# Lipo_Module.net
KiCad netlist of a schematic drawn in EAGLE
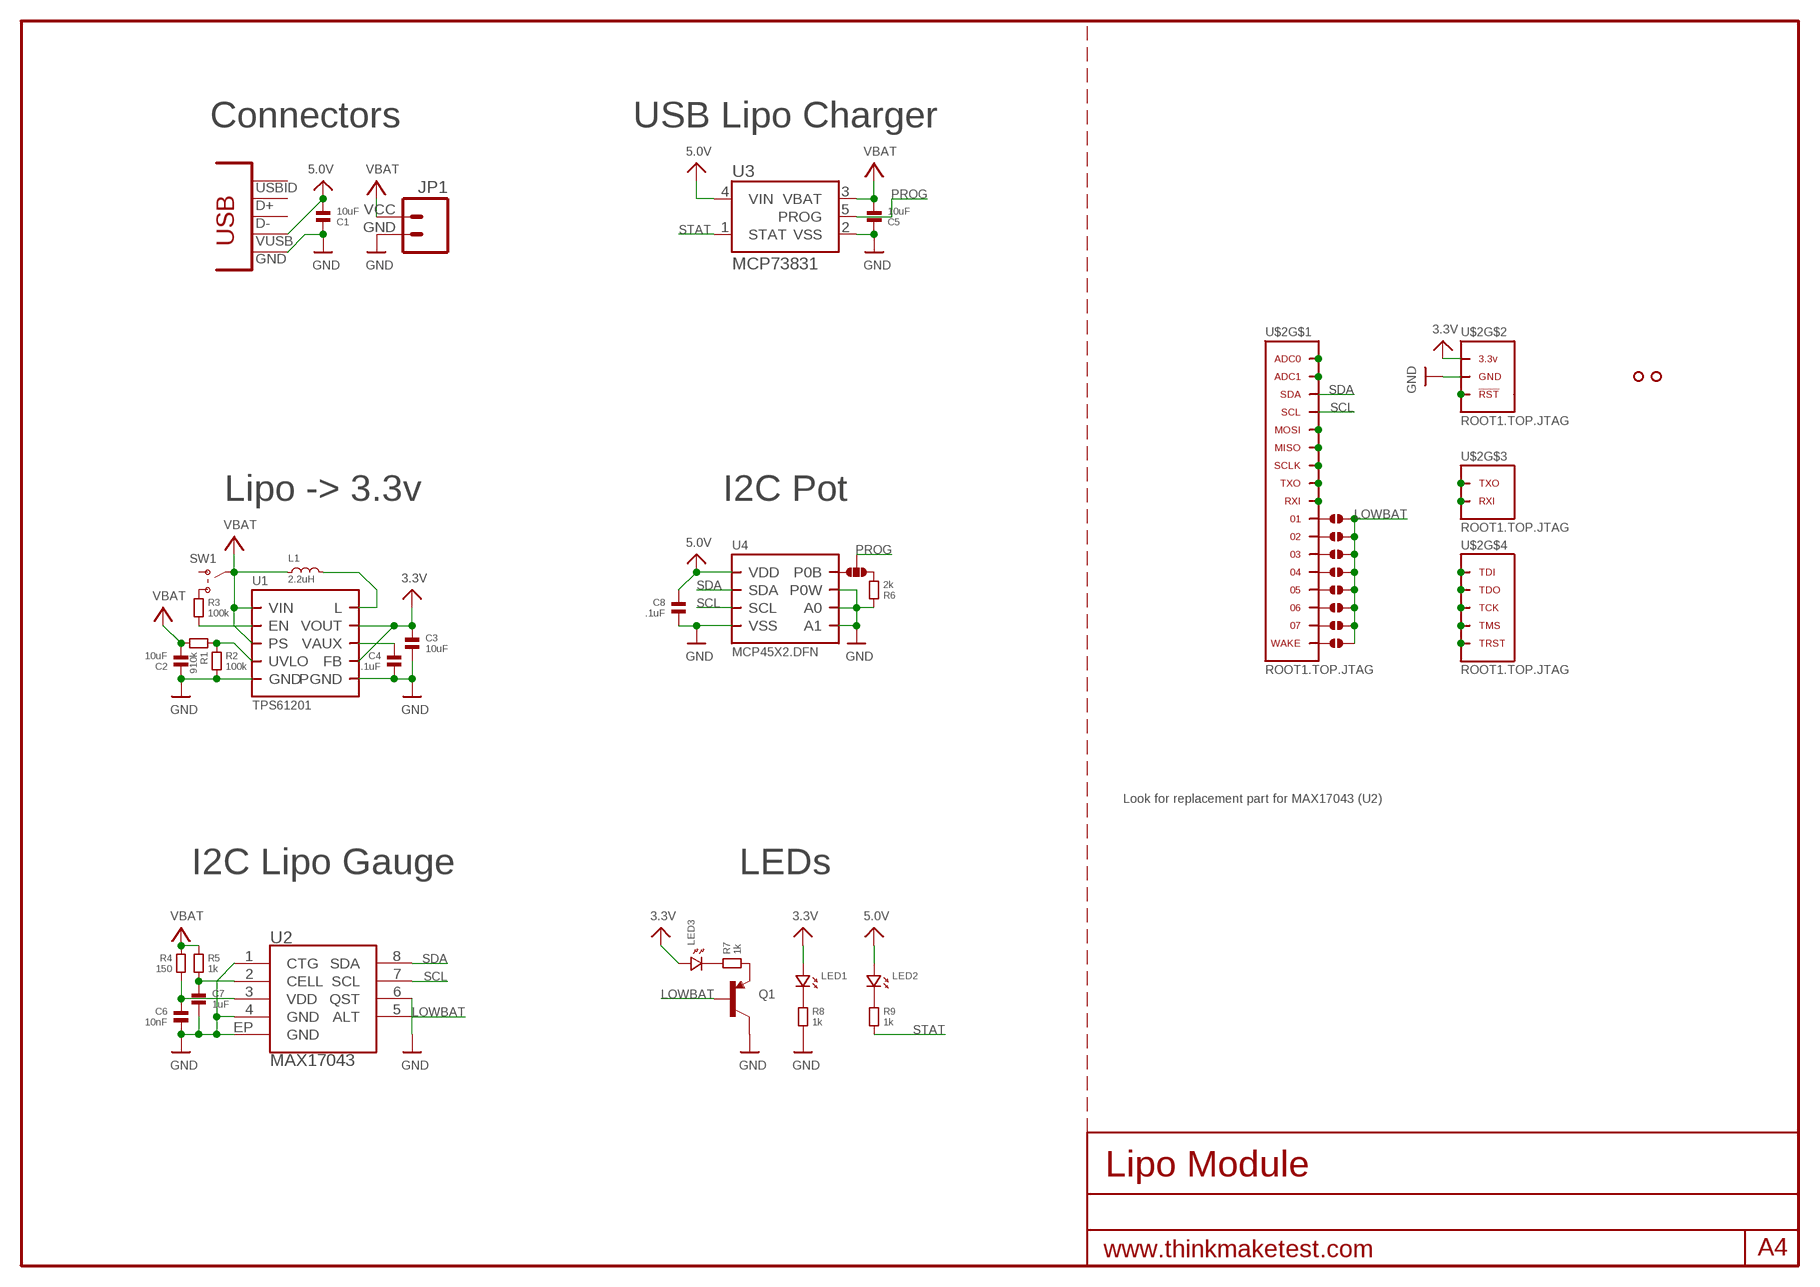
[diagram p0: schematic, sheet 1]

(export (version "E")
  (design (tool "Eeschema 10.0.6"))
  (components
    (comp (ref "C1")
      (value "10uF")
      (footprint "eagle-import:0805")
      (libsource (lib "eagle-import") (part "CAPACITOR.0805"))
    )
    (comp (ref "C2")
      (value "10uF")
      (footprint "eagle-import:0805")
      (libsource (lib "eagle-import") (part "CAPACITOR.0805"))
    )
    (comp (ref "C3")
      (value "10uF")
      (footprint "eagle-import:0805")
      (libsource (lib "eagle-import") (part "CAPACITOR.0805"))
    )
    (comp (ref "C4")
      (value ".1uF")
      (footprint "eagle-import:0603")
      (libsource (lib "eagle-import") (part "CAPACITOR.0603"))
    )
    (comp (ref "C5")
      (value "10uF")
      (footprint "eagle-import:0805")
      (libsource (lib "eagle-import") (part "CAPACITOR.0805"))
    )
    (comp (ref "C6")
      (value "10nF")
      (footprint "eagle-import:0603")
      (libsource (lib "eagle-import") (part "CAPACITOR.0603"))
    )
    (comp (ref "C7")
      (value "1uF")
      (footprint "eagle-import:0603")
      (libsource (lib "eagle-import") (part "CAPACITOR.0603"))
    )
    (comp (ref "C8")
      (value ".1uF")
      (footprint "eagle-import:0603")
      (libsource (lib "eagle-import") (part "CAPACITOR.0603"))
    )
    (comp (ref "J1")
      (value "SOLDERJUMPER.3.LRG.23")
      (footprint "eagle-import:3.LRG.23")
      (libsource (lib "eagle-import") (part "SOLDERJUMPER.3.LRG.23"))
    )
    (comp (ref "J2")
      (value "SOLDERJUMPER.2.SML")
      (footprint "eagle-import:2.SML")
      (libsource (lib "eagle-import") (part "SOLDERJUMPER.2.SML"))
    )
    (comp (ref "J3")
      (value "SOLDERJUMPER.2.SML")
      (footprint "eagle-import:2.SML")
      (libsource (lib "eagle-import") (part "SOLDERJUMPER.2.SML"))
    )
    (comp (ref "J4")
      (value "SOLDERJUMPER.2.SML")
      (footprint "eagle-import:2.SML")
      (libsource (lib "eagle-import") (part "SOLDERJUMPER.2.SML"))
    )
    (comp (ref "J5")
      (value "SOLDERJUMPER.2.SML")
      (footprint "eagle-import:2.SML")
      (libsource (lib "eagle-import") (part "SOLDERJUMPER.2.SML"))
    )
    (comp (ref "J6")
      (value "SOLDERJUMPER.2.SML")
      (footprint "eagle-import:2.SML")
      (libsource (lib "eagle-import") (part "SOLDERJUMPER.2.SML"))
    )
    (comp (ref "J7")
      (value "SOLDERJUMPER.2.SML")
      (footprint "eagle-import:2.SML")
      (libsource (lib "eagle-import") (part "SOLDERJUMPER.2.SML"))
    )
    (comp (ref "J8")
      (value "SOLDERJUMPER.2.SML")
      (footprint "eagle-import:2.SML")
      (libsource (lib "eagle-import") (part "SOLDERJUMPER.2.SML"))
    )
    (comp (ref "J9")
      (value "SOLDERJUMPER.2.SML")
      (footprint "eagle-import:2.SML")
      (libsource (lib "eagle-import") (part "SOLDERJUMPER.2.SML"))
    )
    (comp (ref "JP1")
      (value "M024UCON-15767")
      (footprint "eagle-import:JST-2-SMD-VERT")
      (libsource (lib "eagle-import") (part "M024UCON-15767"))
    )
    (comp (ref "L1")
      (value "2.2uH")
      (footprint "eagle-import:SRN3015")
      (libsource (lib "eagle-import") (part "INDUCTOR-SRN3015"))
    )
    (comp (ref "LED1")
      (value "LED.0603")
      (footprint "eagle-import:0603.LED")
      (libsource (lib "eagle-import") (part "LED.0603"))
    )
    (comp (ref "LED2")
      (value "LED.0603")
      (footprint "eagle-import:0603.LED")
      (libsource (lib "eagle-import") (part "LED.0603"))
    )
    (comp (ref "LED3")
      (value "LED.0603")
      (footprint "eagle-import:0603.LED")
      (libsource (lib "eagle-import") (part "LED.0603"))
    )
    (comp (ref "Q1")
      (value "TRANSISTOR_PNPSOT23-REFLOW")
      (footprint "eagle-import:SOT23-R")
      (libsource (lib "eagle-import") (part "TRANSISTOR_PNPSOT23-REFLOW"))
    )
    (comp (ref "R1")
      (value "910k")
      (footprint "eagle-import:0603")
      (libsource (lib "eagle-import") (part "RESISTOR.0603"))
    )
    (comp (ref "R2")
      (value "100k")
      (footprint "eagle-import:0603")
      (libsource (lib "eagle-import") (part "RESISTOR.0603"))
    )
    (comp (ref "R3")
      (value "100k")
      (footprint "eagle-import:0603")
      (libsource (lib "eagle-import") (part "RESISTOR.0603"))
    )
    (comp (ref "R4")
      (value "150")
      (footprint "eagle-import:0603")
      (libsource (lib "eagle-import") (part "RESISTOR.0603"))
    )
    (comp (ref "R5")
      (value "1k")
      (footprint "eagle-import:0603")
      (libsource (lib "eagle-import") (part "RESISTOR.0603"))
    )
    (comp (ref "R6")
      (value "2k")
      (footprint "eagle-import:0603")
      (libsource (lib "eagle-import") (part "RESISTOR.0603"))
    )
    (comp (ref "R7")
      (value "1k")
      (footprint "eagle-import:0603")
      (libsource (lib "eagle-import") (part "RESISTOR.0603"))
    )
    (comp (ref "R8")
      (value "1k")
      (footprint "eagle-import:0603")
      (libsource (lib "eagle-import") (part "RESISTOR.0603"))
    )
    (comp (ref "R9")
      (value "1k")
      (footprint "eagle-import:0603")
      (libsource (lib "eagle-import") (part "RESISTOR.0603"))
    )
    (comp (ref "SW1")
      (value "SSSS810701")
      (footprint "eagle-import:SSSS810701")
      (libsource (lib "eagle-import") (part "SSSS810701"))
    )
    (comp (ref "U$2")
      (value "ROOT1.TOP.JTAG")
      (footprint "eagle-import:ROOT1.TOP")
      (libsource (lib "eagle-import") (part "ROOT1.TOP.JTAG"))
    )
    (comp (ref "U$3")
      (value "HOLE.2MM")
      (footprint "eagle-import:2MM")
      (libsource (lib "eagle-import") (part "HOLE.2MM"))
    )
    (comp (ref "U$4")
      (value "HOLE.2MM")
      (footprint "eagle-import:2MM")
      (libsource (lib "eagle-import") (part "HOLE.2MM"))
    )
    (comp (ref "U1")
      (value "TPS61201")
      (footprint "eagle-import:DRC")
      (libsource (lib "eagle-import") (part "TPS6120X"))
    )
    (comp (ref "U2")
      (value "MAX17043")
      (footprint "eagle-import:TDFN-8")
      (libsource (lib "eagle-import") (part "MAX1704X"))
    )
    (comp (ref "U3")
      (value "MCP73831")
      (footprint "eagle-import:SOT23-5")
      (libsource (lib "eagle-import") (part "MCP73831"))
    )
    (comp (ref "U4")
      (value "MCP45X2.DFN")
      (footprint "eagle-import:DFN-8.3X3.PAD")
      (libsource (lib "eagle-import") (part "MCP45X2.DFN"))
    )
    (comp (ref "USB1")
      (value "CON-USB-F-MICRO-B")
      (footprint "eagle-import:CONN_USB_MICRO-B")
      (libsource (lib "eagle-import") (part "CON-USB-F-MICRO-B"))
    )
  )
  (nets
    (net (code "1") (name "/LOWBAT") (class "Default")
      (node (ref "J2") (pin "2") (pinfunction "2_2") (pintype "bidirectional"))
      (node (ref "J3") (pin "2") (pinfunction "2_2") (pintype "bidirectional"))
      (node (ref "J4") (pin "2") (pinfunction "2_2") (pintype "bidirectional"))
      (node (ref "J5") (pin "2") (pinfunction "2_2") (pintype "bidirectional"))
      (node (ref "J6") (pin "2") (pinfunction "2_2") (pintype "bidirectional"))
      (node (ref "J7") (pin "2") (pinfunction "2_2") (pintype "bidirectional"))
      (node (ref "J8") (pin "2") (pinfunction "2_2") (pintype "bidirectional"))
      (node (ref "J9") (pin "2") (pinfunction "2_2") (pintype "bidirectional"))
      (node (ref "Q1") (pin "1") (pinfunction "B_1") (pintype "passive"))
      (node (ref "U2") (pin "5") (pinfunction "ALT_5") (pintype "bidirectional"))
    )
    (net (code "2") (name "/PROG") (class "Default")
      (node (ref "J1") (pin "2") (pinfunction "2_2") (pintype "bidirectional"))
      (node (ref "U3") (pin "5") (pinfunction "PROG_5") (pintype "input"))
    )
    (net (code "3") (name "/SCL") (class "Default")
      (node (ref "U$2") (pin "SCL") (pinfunction "SCL_SCL") (pintype "bidirectional"))
      (node (ref "U2") (pin "7") (pinfunction "SCL_7") (pintype "bidirectional"))
      (node (ref "U4") (pin "2") (pinfunction "SCL_2") (pintype "bidirectional"))
    )
    (net (code "4") (name "/SDA") (class "Default")
      (node (ref "U$2") (pin "SDA") (pinfunction "SDA_SDA") (pintype "bidirectional"))
      (node (ref "U2") (pin "8") (pinfunction "SDA_8") (pintype "bidirectional"))
      (node (ref "U4") (pin "3") (pinfunction "SDA_3") (pintype "bidirectional"))
    )
    (net (code "5") (name "/STAT") (class "Default")
      (node (ref "R9") (pin "2") (pinfunction "2_2") (pintype "bidirectional"))
      (node (ref "U3") (pin "1") (pinfunction "STAT_1") (pintype "output"))
    )
    (net (code "6") (name "3.3V") (class "Default")
      (node (ref "C3") (pin "1") (pinfunction "1_1") (pintype "bidirectional"))
      (node (ref "LED1") (pin "P$1") (pinfunction "1_P$1") (pintype "bidirectional"))
      (node (ref "LED3") (pin "P$1") (pinfunction "1_P$1") (pintype "bidirectional"))
      (node (ref "U$2") (pin "3.3V@1") (pinfunction "3.3V_3.3V@1") (pintype "bidirectional"))
      (node (ref "U$2") (pin "3.3V@10") (pinfunction "3.3V_3.3V@10") (pintype "bidirectional"))
      (node (ref "U$2") (pin "3.3V@11") (pinfunction "3.3V_3.3V@11") (pintype "bidirectional"))
      (node (ref "U$2") (pin "3.3V@12") (pinfunction "3.3V_3.3V@12") (pintype "bidirectional"))
      (node (ref "U$2") (pin "3.3V@2") (pinfunction "3.3V_3.3V@2") (pintype "bidirectional"))
      (node (ref "U$2") (pin "3.3V@3") (pinfunction "3.3V_3.3V@3") (pintype "bidirectional"))
      (node (ref "U$2") (pin "3.3V@4") (pinfunction "3.3V_3.3V@4") (pintype "bidirectional"))
      (node (ref "U$2") (pin "3.3V@5") (pinfunction "3.3V_3.3V@5") (pintype "bidirectional"))
      (node (ref "U$2") (pin "3.3V@6") (pinfunction "3.3V_3.3V@6") (pintype "bidirectional"))
      (node (ref "U$2") (pin "3.3V@7") (pinfunction "3.3V_3.3V@7") (pintype "bidirectional"))
      (node (ref "U$2") (pin "3.3V@8") (pinfunction "3.3V_3.3V@8") (pintype "bidirectional"))
      (node (ref "U$2") (pin "3.3V@9") (pinfunction "3.3V_3.3V@9") (pintype "bidirectional"))
      (node (ref "U1") (pin "10") (pinfunction "FB_10") (pintype "bidirectional"))
      (node (ref "U1") (pin "2") (pinfunction "VOUT_2") (pintype "bidirectional"))
    )
    (net (code "7") (name "5.0V") (class "Default")
      (node (ref "C1") (pin "2") (pinfunction "2_2") (pintype "bidirectional"))
      (node (ref "C8") (pin "1") (pinfunction "1_1") (pintype "bidirectional"))
      (node (ref "LED2") (pin "P$1") (pinfunction "1_P$1") (pintype "bidirectional"))
      (node (ref "U3") (pin "4") (pinfunction "VIN_4") (pintype "power_in"))
      (node (ref "U4") (pin "8") (pinfunction "VDD_8") (pintype "bidirectional"))
      (node (ref "USB1") (pin "P1") (pinfunction "VUSB_P1") (pintype "bidirectional"))
    )
    (net (code "8") (name "GND") (class "Default")
      (node (ref "C1") (pin "1") (pinfunction "1_1") (pintype "bidirectional"))
      (node (ref "C2") (pin "1") (pinfunction "1_1") (pintype "bidirectional"))
      (node (ref "C3") (pin "2") (pinfunction "2_2") (pintype "bidirectional"))
      (node (ref "C4") (pin "2") (pinfunction "2_2") (pintype "bidirectional"))
      (node (ref "C5") (pin "1") (pinfunction "1_1") (pintype "bidirectional"))
      (node (ref "C6") (pin "2") (pinfunction "2_2") (pintype "bidirectional"))
      (node (ref "C7") (pin "2") (pinfunction "2_2") (pintype "bidirectional"))
      (node (ref "C8") (pin "2") (pinfunction "2_2") (pintype "bidirectional"))
      (node (ref "JP1") (pin "GND") (pinfunction "1_GND") (pintype "passive"))
      (node (ref "Q1") (pin "3") (pinfunction "C_3") (pintype "passive"))
      (node (ref "R2") (pin "2") (pinfunction "2_2") (pintype "bidirectional"))
      (node (ref "R6") (pin "1") (pinfunction "1_1") (pintype "bidirectional"))
      (node (ref "R8") (pin "2") (pinfunction "2_2") (pintype "bidirectional"))
      (node (ref "U$2") (pin "GND@1") (pinfunction "GND_GND@1") (pintype "bidirectional"))
      (node (ref "U$2") (pin "GND@10") (pinfunction "GND_GND@10") (pintype "bidirectional"))
      (node (ref "U$2") (pin "GND@11") (pinfunction "GND_GND@11") (pintype "bidirectional"))
      (node (ref "U$2") (pin "GND@12") (pinfunction "GND_GND@12") (pintype "bidirectional"))
      (node (ref "U$2") (pin "GND@13") (pinfunction "GND_GND@13") (pintype "bidirectional"))
      (node (ref "U$2") (pin "GND@2") (pinfunction "GND_GND@2") (pintype "bidirectional"))
      (node (ref "U$2") (pin "GND@3") (pinfunction "GND_GND@3") (pintype "bidirectional"))
      (node (ref "U$2") (pin "GND@4") (pinfunction "GND_GND@4") (pintype "bidirectional"))
      (node (ref "U$2") (pin "GND@5") (pinfunction "GND_GND@5") (pintype "bidirectional"))
      (node (ref "U$2") (pin "GND@6") (pinfunction "GND_GND@6") (pintype "bidirectional"))
      (node (ref "U$2") (pin "GND@7") (pinfunction "GND_GND@7") (pintype "bidirectional"))
      (node (ref "U$2") (pin "GND@8") (pinfunction "GND_GND@8") (pintype "bidirectional"))
      (node (ref "U$2") (pin "GND@9") (pinfunction "GND_GND@9") (pintype "bidirectional"))
      (node (ref "U1") (pin "4") (pinfunction "PGND_4") (pintype "bidirectional"))
      (node (ref "U1") (pin "9") (pinfunction "GND_9") (pintype "bidirectional"))
      (node (ref "U1") (pin "PAD") (pinfunction "PGND_PAD") (pintype "bidirectional"))
      (node (ref "U2") (pin "1") (pinfunction "CTG_1") (pintype "bidirectional"))
      (node (ref "U2") (pin "4") (pinfunction "GND_4") (pintype "bidirectional"))
      (node (ref "U2") (pin "6") (pinfunction "QST_6") (pintype "bidirectional"))
      (node (ref "U2") (pin "EP") (pinfunction "GND_EP") (pintype "bidirectional"))
      (node (ref "U3") (pin "2") (pinfunction "VSS_2") (pintype "power_in"))
      (node (ref "U4") (pin "1") (pinfunction "A0_1") (pintype "bidirectional"))
      (node (ref "U4") (pin "4") (pinfunction "VSS_4") (pintype "bidirectional"))
      (node (ref "U4") (pin "5") (pinfunction "P0W_5") (pintype "bidirectional"))
      (node (ref "U4") (pin "7") (pinfunction "A1_7") (pintype "bidirectional"))
      (node (ref "U4") (pin "PAD") (pinfunction "VSS_PAD") (pintype "bidirectional"))
      (node (ref "USB1") (pin "P5") (pinfunction "GND_P5") (pintype "bidirectional"))
    )
    (net (code "9") (name "Net-(J1-Pad3)") (class "Default")
      (node (ref "J1") (pin "3") (pinfunction "3_3") (pintype "bidirectional"))
      (node (ref "R6") (pin "2") (pinfunction "2_2") (pintype "bidirectional"))
    )
    (net (code "10") (name "Net-(J2-Pad1)") (class "Default")
      (node (ref "J2") (pin "1") (pinfunction "1_1") (pintype "bidirectional"))
      (node (ref "U$2") (pin "01") (pinfunction "01_01") (pintype "bidirectional"))
    )
    (net (code "11") (name "Net-(J3-Pad1)") (class "Default")
      (node (ref "J3") (pin "1") (pinfunction "1_1") (pintype "bidirectional"))
      (node (ref "U$2") (pin "02") (pinfunction "02_02") (pintype "bidirectional"))
    )
    (net (code "12") (name "Net-(J4-Pad1)") (class "Default")
      (node (ref "J4") (pin "1") (pinfunction "1_1") (pintype "bidirectional"))
      (node (ref "U$2") (pin "03") (pinfunction "03_03") (pintype "bidirectional"))
    )
    (net (code "13") (name "Net-(J5-Pad1)") (class "Default")
      (node (ref "J5") (pin "1") (pinfunction "1_1") (pintype "bidirectional"))
      (node (ref "U$2") (pin "04") (pinfunction "04_04") (pintype "bidirectional"))
    )
    (net (code "14") (name "Net-(J6-Pad1)") (class "Default")
      (node (ref "J6") (pin "1") (pinfunction "1_1") (pintype "bidirectional"))
      (node (ref "U$2") (pin "05") (pinfunction "05_05") (pintype "bidirectional"))
    )
    (net (code "15") (name "Net-(J7-Pad1)") (class "Default")
      (node (ref "J7") (pin "1") (pinfunction "1_1") (pintype "bidirectional"))
      (node (ref "U$2") (pin "06") (pinfunction "06_06") (pintype "bidirectional"))
    )
    (net (code "16") (name "Net-(J8-Pad1)") (class "Default")
      (node (ref "J8") (pin "1") (pinfunction "1_1") (pintype "bidirectional"))
      (node (ref "U$2") (pin "07") (pinfunction "07_07") (pintype "bidirectional"))
    )
    (net (code "17") (name "Net-(J9-Pad1)") (class "Default")
      (node (ref "J9") (pin "1") (pinfunction "1_1") (pintype "bidirectional"))
      (node (ref "U$2") (pin "WAKE") (pinfunction "WAKE_WAKE") (pintype "bidirectional"))
    )
    (net (code "18") (name "Net-(LED1-2)") (class "Default")
      (node (ref "LED1") (pin "P$2") (pinfunction "2_P$2") (pintype "bidirectional"))
      (node (ref "R8") (pin "1") (pinfunction "1_1") (pintype "bidirectional"))
    )
    (net (code "19") (name "Net-(LED2-2)") (class "Default")
      (node (ref "LED2") (pin "P$2") (pinfunction "2_P$2") (pintype "bidirectional"))
      (node (ref "R9") (pin "1") (pinfunction "1_1") (pintype "bidirectional"))
    )
    (net (code "20") (name "Net-(LED3-2)") (class "Default")
      (node (ref "LED3") (pin "P$2") (pinfunction "2_P$2") (pintype "bidirectional"))
      (node (ref "R7") (pin "1") (pinfunction "1_1") (pintype "bidirectional"))
    )
    (net (code "21") (name "Net-(Q1-E)") (class "Default")
      (node (ref "Q1") (pin "2") (pinfunction "E_2") (pintype "passive"))
      (node (ref "R7") (pin "2") (pinfunction "2_2") (pintype "bidirectional"))
    )
    (net (code "22") (name "Net-(SW1-B)") (class "Default")
      (node (ref "R3") (pin "1") (pinfunction "1_1") (pintype "bidirectional"))
      (node (ref "SW1") (pin "1") (pinfunction "B_1") (pintype "bidirectional"))
    )
    (net (code "23") (name "Net-(U1-EN)") (class "Default")
      (node (ref "R3") (pin "2") (pinfunction "2_2") (pintype "bidirectional"))
      (node (ref "U1") (pin "6") (pinfunction "EN_6") (pintype "bidirectional"))
    )
    (net (code "24") (name "Net-(U1-L)") (class "Default")
      (node (ref "L1") (pin "2") (pinfunction "2_2") (pintype "passive"))
      (node (ref "U1") (pin "3") (pinfunction "L_3") (pintype "bidirectional"))
    )
    (net (code "25") (name "Net-(U1-UVLO)") (class "Default")
      (node (ref "R1") (pin "1") (pinfunction "1_1") (pintype "bidirectional"))
      (node (ref "R2") (pin "1") (pinfunction "1_1") (pintype "bidirectional"))
      (node (ref "U1") (pin "7") (pinfunction "UVLO_7") (pintype "bidirectional"))
    )
    (net (code "26") (name "Net-(U1-VAUX)") (class "Default")
      (node (ref "C4") (pin "1") (pinfunction "1_1") (pintype "bidirectional"))
      (node (ref "U1") (pin "1") (pinfunction "VAUX_1") (pintype "bidirectional"))
    )
    (net (code "27") (name "Net-(U2-CELL)") (class "Default")
      (node (ref "C7") (pin "1") (pinfunction "1_1") (pintype "bidirectional"))
      (node (ref "R5") (pin "2") (pinfunction "2_2") (pintype "bidirectional"))
      (node (ref "U2") (pin "2") (pinfunction "CELL_2") (pintype "bidirectional"))
    )
    (net (code "28") (name "Net-(U2-VDD)") (class "Default")
      (node (ref "C6") (pin "1") (pinfunction "1_1") (pintype "bidirectional"))
      (node (ref "R4") (pin "2") (pinfunction "2_2") (pintype "bidirectional"))
      (node (ref "U2") (pin "3") (pinfunction "VDD_3") (pintype "bidirectional"))
    )
    (net (code "29") (name "Net-(U4-P0B)") (class "Default")
      (node (ref "J1") (pin "1") (pinfunction "1_1") (pintype "bidirectional"))
      (node (ref "U4") (pin "6") (pinfunction "P0B_6") (pintype "bidirectional"))
    )
    (net (code "30") (name "VBAT") (class "Default")
      (node (ref "C2") (pin "2") (pinfunction "2_2") (pintype "bidirectional"))
      (node (ref "C5") (pin "2") (pinfunction "2_2") (pintype "bidirectional"))
      (node (ref "JP1") (pin "VCC") (pinfunction "2_VCC") (pintype "passive"))
      (node (ref "L1") (pin "1") (pinfunction "1_1") (pintype "passive"))
      (node (ref "R1") (pin "2") (pinfunction "2_2") (pintype "bidirectional"))
      (node (ref "R4") (pin "1") (pinfunction "1_1") (pintype "bidirectional"))
      (node (ref "R5") (pin "1") (pinfunction "1_1") (pintype "bidirectional"))
      (node (ref "SW1") (pin "2") (pinfunction "COM_2") (pintype "bidirectional"))
      (node (ref "U1") (pin "5") (pinfunction "VIN_5") (pintype "bidirectional"))
      (node (ref "U1") (pin "8") (pinfunction "PS_8") (pintype "bidirectional"))
      (node (ref "U3") (pin "3") (pinfunction "VBAT_3") (pintype "power_in"))
    )
    (net (code "31") (name "unconnected-(SW1-A-Pad3)") (class "Default")
      (node (ref "SW1") (pin "3") (pinfunction "A_3") (pintype "bidirectional"))
    )
    (net (code "32") (name "unconnected-(U$2-PadADC0)") (class "Default")
      (node (ref "U$2") (pin "ADC0") (pinfunction "ADC0_ADC0") (pintype "bidirectional"))
    )
    (net (code "33") (name "unconnected-(U$2-PadADC1)") (class "Default")
      (node (ref "U$2") (pin "ADC1") (pinfunction "ADC1_ADC1") (pintype "bidirectional"))
    )
    (net (code "34") (name "unconnected-(U$2-PadMISO)") (class "Default")
      (node (ref "U$2") (pin "MISO") (pinfunction "MISO_MISO") (pintype "bidirectional"))
    )
    (net (code "35") (name "unconnected-(U$2-PadMOSI)") (class "Default")
      (node (ref "U$2") (pin "MOSI") (pinfunction "MOSI_MOSI") (pintype "bidirectional"))
    )
    (net (code "36") (name "unconnected-(U$2-PadRXI)") (class "Default")
      (node (ref "U$2") (pin "RXI") (pinfunction "RXI_RXI") (pintype "bidirectional"))
    )
    (net (code "37") (name "unconnected-(U$2-PadSCLK)") (class "Default")
      (node (ref "U$2") (pin "SCLK") (pinfunction "SCLK_SCLK") (pintype "bidirectional"))
    )
    (net (code "38") (name "unconnected-(U$2-PadTCK)") (class "Default")
      (node (ref "U$2") (pin "TCK") (pinfunction "TCK_TCK") (pintype "bidirectional"))
    )
    (net (code "39") (name "unconnected-(U$2-PadTDI)") (class "Default")
      (node (ref "U$2") (pin "TDI") (pinfunction "TDI_TDI") (pintype "bidirectional"))
    )
    (net (code "40") (name "unconnected-(U$2-PadTDO)") (class "Default")
      (node (ref "U$2") (pin "TDO") (pinfunction "TDO_TDO") (pintype "bidirectional"))
    )
    (net (code "41") (name "unconnected-(U$2-PadTMS)") (class "Default")
      (node (ref "U$2") (pin "TMS") (pinfunction "TMS_TMS") (pintype "bidirectional"))
    )
    (net (code "42") (name "unconnected-(U$2-PadTRST)") (class "Default")
      (node (ref "U$2") (pin "TRST") (pinfunction "TRST_TRST") (pintype "bidirectional"))
    )
    (net (code "43") (name "unconnected-(U$2-PadTXO)") (class "Default")
      (node (ref "U$2") (pin "TXO") (pinfunction "TXO_TXO") (pintype "bidirectional"))
    )
    (net (code "44") (name "unconnected-(U$2B-~{RST}-PadRST)") (class "Default")
      (node (ref "U$2") (pin "RST") (pinfunction "~{RST}_RST") (pintype "bidirectional"))
    )
    (net (code "45") (name "unconnected-(U$2C-RXI-PadRXI.DBG)") (class "Default")
      (node (ref "U$2") (pin "RXI.DBG") (pinfunction "RXI_RXI.DBG") (pintype "bidirectional"))
    )
    (net (code "46") (name "unconnected-(U$2C-TXO-PadTXO.DBG)") (class "Default")
      (node (ref "U$2") (pin "TXO.DBG") (pinfunction "TXO_TXO.DBG") (pintype "bidirectional"))
    )
    (net (code "47") (name "unconnected-(USB1B-D+-PadP3)") (class "Default")
      (node (ref "USB1") (pin "P3") (pinfunction "D+_P3") (pintype "bidirectional"))
    )
    (net (code "48") (name "unconnected-(USB1B-D--PadP2)") (class "Default")
      (node (ref "USB1") (pin "P2") (pinfunction "D-_P2") (pintype "bidirectional"))
    )
    (net (code "49") (name "unconnected-(USB1B-USBID-PadP4)") (class "Default")
      (node (ref "USB1") (pin "P4") (pinfunction "USBID_P4") (pintype "bidirectional"))
    )
  )
)
